# SFPplusConn.net
KiCad netlist of a schematic drawn in Altium Designer
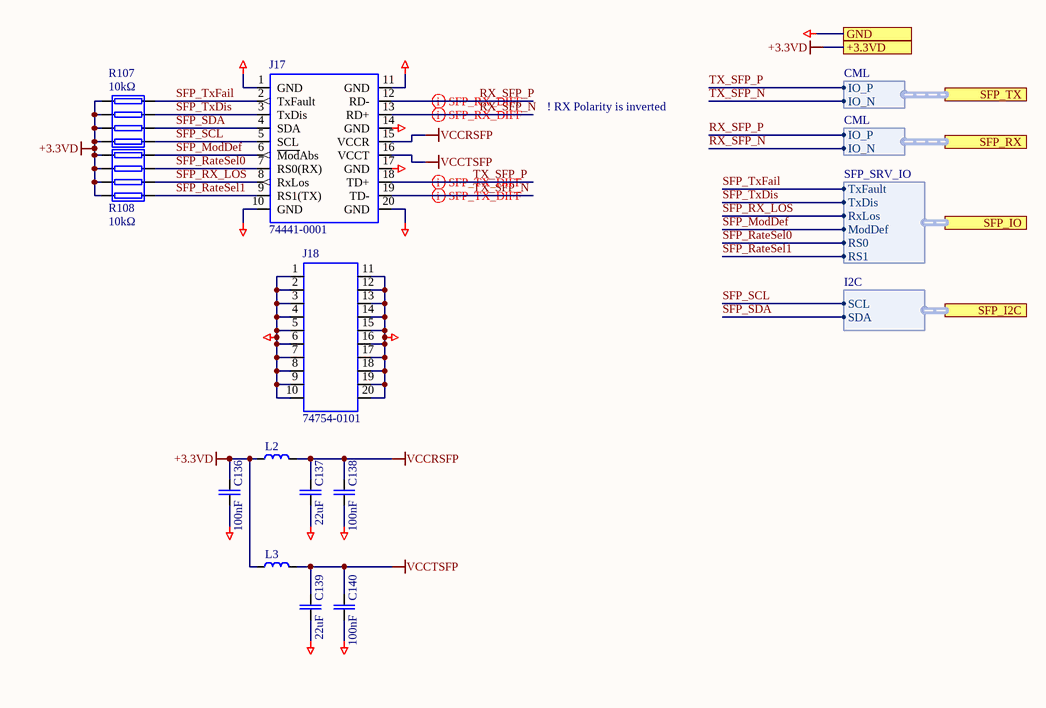
[diagram p0: SFPplusConn.SchDoc]

(export (version "E")
  (design (tool "Eeschema 10.0.6"))
  (components
    (comp (ref "C136")
      (value "100nF")
      (footprint "CAPC1608N")
      (description "Generic ceramic SMD capacitor")
      (fields (field (name "MAINTAINER") "Evgeniy Kotov"))
      (libsource (lib "[Capacitors] Capacitors SMD") (part "CAPC"))
    )
    (comp (ref "C137")
      (value "22uF")
      (footprint "CAPC2012N")
      (description "Generic ceramic SMD capacitor")
      (fields (field (name "MAINTAINER") "Evgeniy Kotov"))
      (libsource (lib "[Capacitors] Capacitors SMD") (part "CAPC"))
    )
    (comp (ref "C138")
      (value "100nF")
      (footprint "CAPC1608N")
      (description "Generic ceramic SMD capacitor")
      (fields (field (name "MAINTAINER") "Evgeniy Kotov"))
      (libsource (lib "[Capacitors] Capacitors SMD") (part "CAPC"))
    )
    (comp (ref "C139")
      (value "22uF")
      (footprint "CAPC2012N")
      (description "Generic ceramic SMD capacitor")
      (fields (field (name "MAINTAINER") "Evgeniy Kotov"))
      (libsource (lib "[Capacitors] Capacitors SMD") (part "CAPC"))
    )
    (comp (ref "C140")
      (value "100nF")
      (footprint "CAPC1608N")
      (description "Generic ceramic SMD capacitor")
      (fields (field (name "MAINTAINER") "Evgeniy Kotov"))
      (libsource (lib "[Capacitors] Capacitors SMD") (part "CAPC"))
    )
    (comp (ref "J17")
      (value "74441-0001")
      (footprint "MOLEX_74441-0001")
      (description "CONN SFP+ RCPT 20POS SLD R/A SMD")
      (libsource (lib "[Connectors] Miscellaneous") (part "MOLEX-74441-0001"))
    )
    (comp (ref "J18")
      (value "74754-0101")
      (footprint "MOLEX_74737-0111")
      (description "SFP+ Cage, Single Port, Height 10.85 mm, Tail Height 3.05 mm, -40 to 85 degC, RoHS, Tray")
      (libsource (lib "[Connectors] Miscellaneous") (part "MOLX-74754-0101"))
    )
    (comp (ref "L2")
      (value "BLM21PG221SN1")
      (footprint "INDC2012N")
      (description "Ferrite Beads, 0805, 220 Ohm, 2A")
      (fields (field (name "TOLERANCE") "25%") (field (name "MAINTAINER") "Evgeniy Kotov"))
      (libsource (lib "[Inductors & Transformers] Inductors SMD") (part "BLM21PG221SN1"))
    )
    (comp (ref "L3")
      (value "BLM21PG221SN1")
      (footprint "INDC2012N")
      (description "Ferrite Beads, 0805, 220 Ohm, 2A")
      (fields (field (name "TOLERANCE") "25%") (field (name "MAINTAINER") "Evgeniy Kotov"))
      (libsource (lib "[Inductors & Transformers] Inductors SMD") (part "BLM21PG221SN1"))
    )
    (comp (ref "R107")
      (value "10kΩ")
      (footprint "CAY16-J4")
      (fields (field (name "Comment") "CAY16-1002F4LF") (field (name "MAINTAINER") "Anton Pavlenko"))
      (libsource (lib "[Resistors] Resistors SMD") (part "RESPACK4"))
    )
    (comp (ref "R108")
      (value "10kΩ")
      (footprint "CAY16-J4")
      (fields (field (name "Comment") "CAY16-1002F4LF") (field (name "MAINTAINER") "Anton Pavlenko"))
      (libsource (lib "[Resistors] Resistors SMD") (part "RESPACK4"))
    )
  )
  (nets
    (net (code "4") (name "+3.3VD") (class "Default")
      (node (ref "C136") (pin "2") (pintype "passive"))
      (node (ref "L2") (pin "1") (pinfunction "1_1") (pintype "passive"))
      (node (ref "L3") (pin "1") (pinfunction "1_1") (pintype "passive"))
      (node (ref "R107") (pin "1") (pinfunction "1_1") (pintype "passive"))
      (node (ref "R107") (pin "2") (pinfunction "2_2") (pintype "passive"))
      (node (ref "R107") (pin "3") (pinfunction "3_3") (pintype "passive"))
      (node (ref "R107") (pin "4") (pinfunction "4_4") (pintype "passive"))
      (node (ref "R108") (pin "1") (pinfunction "1_1") (pintype "passive"))
      (node (ref "R108") (pin "2") (pinfunction "2_2") (pintype "passive"))
      (node (ref "R108") (pin "3") (pinfunction "3_3") (pintype "passive"))
      (node (ref "R108") (pin "4") (pinfunction "4_4") (pintype "passive"))
    )
    (net (code "5") (name "/RX_SFP_N") (class "Default")
      (node (ref "J17") (pin "13") (pinfunction "RD+_13") (pintype "passive"))
    )
    (net (code "6") (name "/RX_SFP_P") (class "Default")
      (node (ref "J17") (pin "12") (pinfunction "RD-_12") (pintype "passive"))
    )
    (net (code "7") (name "/SFP_ModDef") (class "Default")
      (node (ref "J17") (pin "6") (pinfunction "~{Mod}Abs_6") (pintype "output"))
      (node (ref "R108") (pin "8") (pinfunction "8_8") (pintype "passive"))
    )
    (net (code "8") (name "/SFP_RX_LOS") (class "Default")
      (node (ref "J17") (pin "8") (pinfunction "RxLos_8") (pintype "output"))
      (node (ref "R108") (pin "6") (pinfunction "6_6") (pintype "passive"))
    )
    (net (code "9") (name "/SFP_RateSel0") (class "Default")
      (node (ref "J17") (pin "7") (pinfunction "RS0(RX)_7") (pintype "passive"))
      (node (ref "R108") (pin "7") (pinfunction "7_7") (pintype "passive"))
    )
    (net (code "10") (name "/SFP_RateSel1") (class "Default")
      (node (ref "J17") (pin "9") (pinfunction "RS1(TX)_9") (pintype "passive"))
      (node (ref "R108") (pin "5") (pinfunction "5_5") (pintype "passive"))
    )
    (net (code "11") (name "/SFP_SCL") (class "Default")
      (node (ref "J17") (pin "5") (pinfunction "SCL_5") (pintype "passive"))
      (node (ref "R107") (pin "5") (pinfunction "5_5") (pintype "passive"))
    )
    (net (code "12") (name "/SFP_SDA") (class "Default")
      (node (ref "J17") (pin "4") (pinfunction "SDA_4") (pintype "passive"))
      (node (ref "R107") (pin "6") (pinfunction "6_6") (pintype "passive"))
    )
    (net (code "13") (name "/SFP_TxDis") (class "Default")
      (node (ref "J17") (pin "3") (pinfunction "TxDis_3") (pintype "passive"))
      (node (ref "R107") (pin "7") (pinfunction "7_7") (pintype "passive"))
    )
    (net (code "14") (name "/SFP_TxFail") (class "Default")
      (node (ref "J17") (pin "2") (pinfunction "TxFault_2") (pintype "output"))
      (node (ref "R107") (pin "8") (pinfunction "8_8") (pintype "passive"))
    )
    (net (code "15") (name "/TX_SFP_N") (class "Default")
      (node (ref "J17") (pin "19") (pinfunction "TD-_19") (pintype "passive"))
    )
    (net (code "16") (name "/TX_SFP_P") (class "Default")
      (node (ref "J17") (pin "18") (pinfunction "TD+_18") (pintype "passive"))
    )
    (net (code "20") (name "GND") (class "Default")
      (node (ref "C136") (pin "1") (pintype "passive"))
      (node (ref "C137") (pin "1") (pintype "passive"))
      (node (ref "C138") (pin "1") (pintype "passive"))
      (node (ref "C139") (pin "1") (pintype "passive"))
      (node (ref "C140") (pin "1") (pintype "passive"))
      (node (ref "J17") (pin "1") (pinfunction "GND_1") (pintype "passive"))
      (node (ref "J17") (pin "10") (pinfunction "GND_10") (pintype "passive"))
      (node (ref "J17") (pin "11") (pinfunction "GND_11") (pintype "passive"))
      (node (ref "J17") (pin "14") (pinfunction "GND_14") (pintype "passive"))
      (node (ref "J17") (pin "17") (pinfunction "GND_17") (pintype "passive"))
      (node (ref "J17") (pin "20") (pinfunction "GND_20") (pintype "passive"))
      (node (ref "J18") (pin "1") (pinfunction "1_1") (pintype "passive"))
      (node (ref "J18") (pin "10") (pinfunction "10_10") (pintype "passive"))
      (node (ref "J18") (pin "11") (pinfunction "11_11") (pintype "passive"))
      (node (ref "J18") (pin "12") (pinfunction "12_12") (pintype "passive"))
      (node (ref "J18") (pin "13") (pinfunction "13_13") (pintype "passive"))
      (node (ref "J18") (pin "14") (pinfunction "14_14") (pintype "passive"))
      (node (ref "J18") (pin "15") (pinfunction "15_15") (pintype "passive"))
      (node (ref "J18") (pin "16") (pinfunction "16_16") (pintype "passive"))
      (node (ref "J18") (pin "17") (pinfunction "17_17") (pintype "passive"))
      (node (ref "J18") (pin "18") (pinfunction "18_18") (pintype "passive"))
      (node (ref "J18") (pin "19") (pinfunction "19_19") (pintype "passive"))
      (node (ref "J18") (pin "2") (pinfunction "2_2") (pintype "passive"))
      (node (ref "J18") (pin "20") (pinfunction "20_20") (pintype "passive"))
      (node (ref "J18") (pin "3") (pinfunction "3_3") (pintype "passive"))
      (node (ref "J18") (pin "4") (pinfunction "4_4") (pintype "passive"))
      (node (ref "J18") (pin "5") (pinfunction "5_5") (pintype "passive"))
      (node (ref "J18") (pin "6") (pinfunction "6_6") (pintype "passive"))
      (node (ref "J18") (pin "7") (pinfunction "7_7") (pintype "passive"))
      (node (ref "J18") (pin "8") (pinfunction "8_8") (pintype "passive"))
      (node (ref "J18") (pin "9") (pinfunction "9_9") (pintype "passive"))
    )
    (net (code "21") (name "VCCRSFP") (class "Default")
      (node (ref "C137") (pin "2") (pintype "passive"))
      (node (ref "C138") (pin "2") (pintype "passive"))
      (node (ref "J17") (pin "15") (pinfunction "VCCR_15") (pintype "passive"))
      (node (ref "L2") (pin "2") (pinfunction "2_2") (pintype "passive"))
    )
    (net (code "22") (name "VCCTSFP") (class "Default")
      (node (ref "C139") (pin "2") (pintype "passive"))
      (node (ref "C140") (pin "2") (pintype "passive"))
      (node (ref "J17") (pin "16") (pinfunction "VCCT_16") (pintype "passive"))
      (node (ref "L3") (pin "2") (pinfunction "2_2") (pintype "passive"))
    )
  )
)
